# EVK-IRIS-W1-RMII.net
KiCad netlist of a schematic drawn in Altium Designer
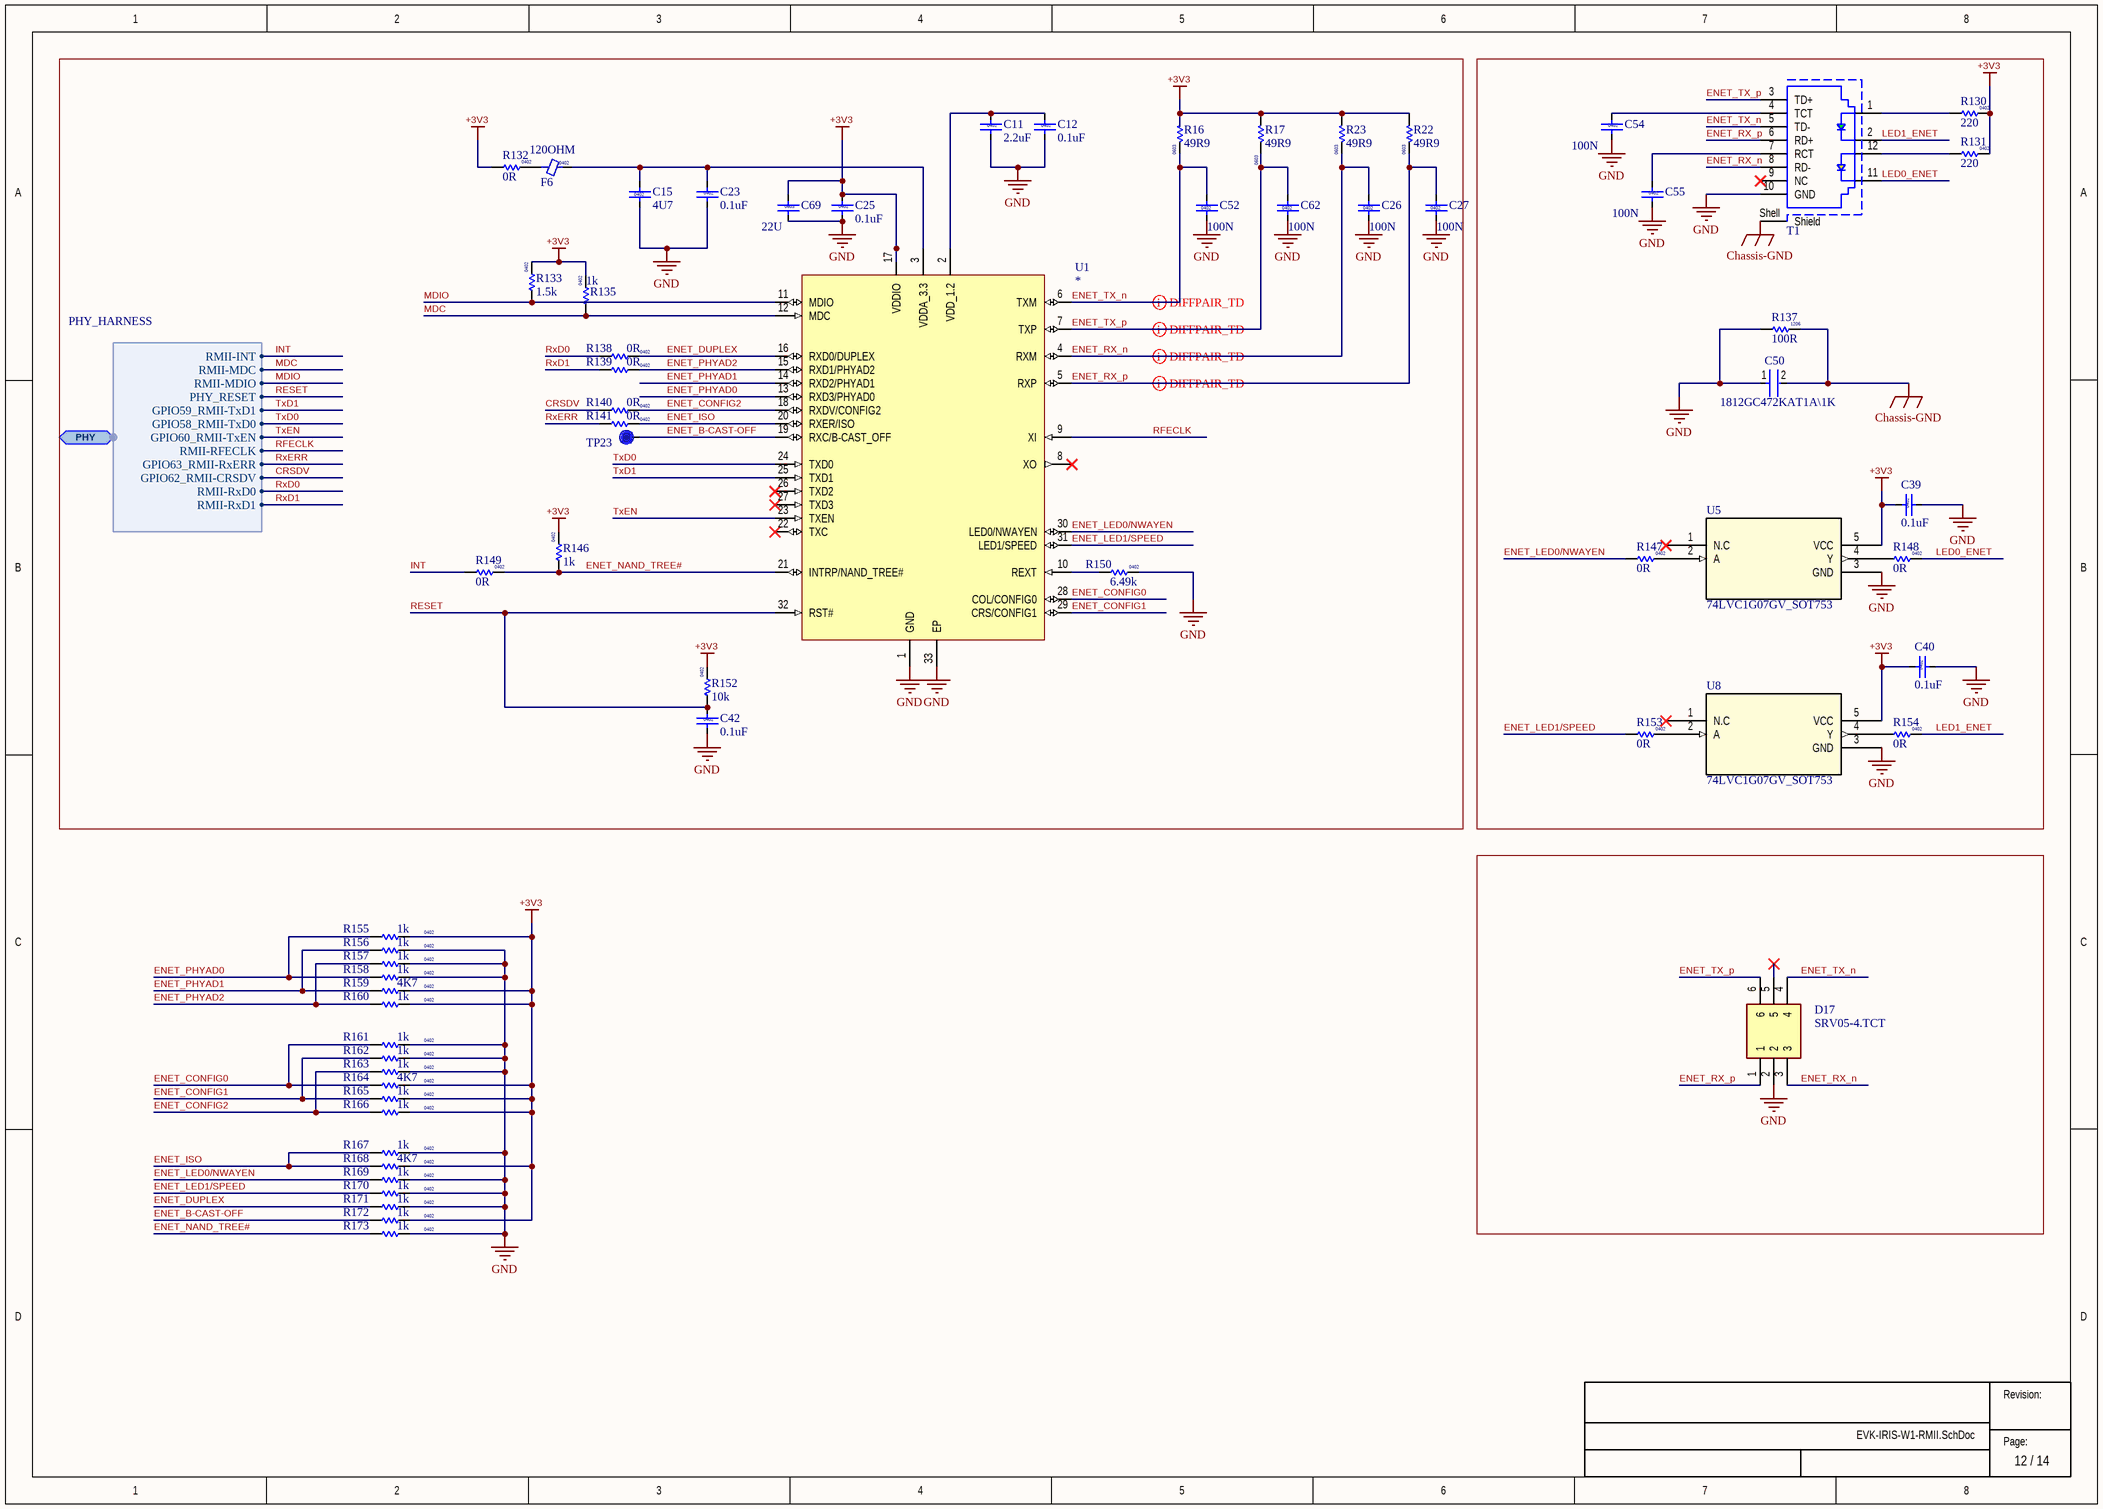
[diagram p0: EVK-IRIS-W1-RMII.SchDoc]

(export (version "E")
  (design (tool "Eeschema 10.0.6"))
  (components
    (comp (ref "C11")
      (value "2.2uF")
      (footprint "Cap 0402 HD")
      (description "Cap, Ceramic 2.2uF 6.3V 10% X5R 0402")
      (fields
        (field (name "SIZE") "0402")
        (field (name "PART NUMBER") "120-00042")
        (field (name "TOLERANCE") "+/- 10%")
      )
      (libsource (lib "Arena_Parts_DB_Lib") (part "Cap Chip"))
    )
    (comp (ref "C12")
      (value "0.1uF")
      (footprint "Cap 0402 HD")
      (description "Cap, Ceramic 0.1uF 10V 10% X5R 0402")
      (fields
        (field (name "SIZE") "0402")
        (field (name "PART NUMBER") "120-00016")
        (field (name "TOLERANCE") "+/- 10%")
      )
      (libsource (lib "Arena_Parts_DB_Lib") (part "Cap Chip"))
    )
    (comp (ref "C15")
      (value "4U7")
      (footprint "Cap_0402_1200Lx700Wx700H_600x600Pad_350G_FLX")
      (description "CAP CER X5R 0402 4U7 20% 10V")
      (fields
        (field (name "SIZE") "0402")
        (field (name "PART NUMBER") "UBXH01-0000243")
        (field (name "TOLERANCE") "20%")
        (field (name "EDITOR") "martin.pilik")
        (field (name "RELEASED BY") "fabrice.bret-dibat")
      )
      (libsource (lib "UBX_Parts_DB_Lib") (part "Cap Chip"))
    )
    (comp (ref "C23")
      (value "0.1uF")
      (footprint "Cap 0402 HD")
      (description "Cap, Ceramic 0.1uF 10V 10% X5R 0402")
      (fields
        (field (name "SIZE") "0402")
        (field (name "PART NUMBER") "120-00016")
        (field (name "TOLERANCE") "+/- 10%")
      )
      (libsource (lib "Arena_Parts_DB_Lib") (part "Cap Chip"))
    )
    (comp (ref "C25")
      (value "0.1uF")
      (footprint "Cap 0402 HD")
      (description "Cap, Ceramic 0.1uF 10V 10% X5R 0402")
      (fields
        (field (name "SIZE") "0402")
        (field (name "PART NUMBER") "120-00016")
        (field (name "TOLERANCE") "+/- 10%")
      )
      (libsource (lib "Arena_Parts_DB_Lib") (part "Cap Chip"))
    )
    (comp (ref "C26")
      (value "100N")
      (footprint "Cap 0402 HD")
      (description "CAP CER X7R 0402 100N 10% 16V")
      (fields
        (field (name "SIZE") "0402")
        (field (name "PART NUMBER") "UBXH01-0000233")
        (field (name "TOLERANCE") "10%")
        (field (name "EDITOR") "philippe.largier")
        (field (name "RELEASED BY") "charlotte.biber")
      )
      (libsource (lib "UBX_Parts_DB_Lib") (part "Cap Chip"))
    )
    (comp (ref "C27")
      (value "100N")
      (footprint "Cap 0402 HD")
      (description "CAP CER X7R 0402 100N 10% 16V")
      (fields
        (field (name "SIZE") "0402")
        (field (name "PART NUMBER") "UBXH01-0000233")
        (field (name "TOLERANCE") "10%")
        (field (name "EDITOR") "philippe.largier")
        (field (name "RELEASED BY") "charlotte.biber")
      )
      (libsource (lib "UBX_Parts_DB_Lib") (part "Cap Chip"))
    )
    (comp (ref "C39")
      (value "0.1uF")
      (footprint "Cap 0402 HD")
      (description "Cap, Ceramic 0.1uF 10V 10% X5R 0402")
      (fields
        (field (name "SIZE") "0402")
        (field (name "PART NUMBER") "120-00016")
        (field (name "TOLERANCE") "+/- 10%")
      )
      (libsource (lib "Arena_Parts_DB_Lib") (part "Cap Chip"))
    )
    (comp (ref "C40")
      (value "0.1uF")
      (footprint "Cap 0402 HD")
      (description "Cap, Ceramic 0.1uF 10V 10% X5R 0402")
      (fields
        (field (name "SIZE") "0402")
        (field (name "PART NUMBER") "120-00016")
        (field (name "TOLERANCE") "+/- 10%")
      )
      (libsource (lib "Arena_Parts_DB_Lib") (part "Cap Chip"))
    )
    (comp (ref "C42")
      (value "0.1uF")
      (footprint "Cap 0402 HD")
      (description "Cap, Ceramic 0.1uF 10V 10% X5R 0402")
      (fields
        (field (name "SIZE") "0402")
        (field (name "PART NUMBER") "120-00016")
        (field (name "TOLERANCE") "+/- 10%")
      )
      (libsource (lib "Arena_Parts_DB_Lib") (part "Cap Chip"))
    )
    (comp (ref "C50")
      (value "1812GC472KAT1~{A}1K")
      (footprint "FP-1812-L_4_6_0_5-W_3_2_0-MFG")
      (description "CAP CER 4700PF 2KV X7R 1812")
      (fields (field (name "VOLTAGE") "2kV") (field (name "TOLERANCE") "10%"))
      (libsource (lib "Altium Content Vault") (part "02cd4be3c70576c341d710602a673aa"))
    )
    (comp (ref "C52")
      (value "100N")
      (footprint "CAP 0402")
      (description "CAP CER X7R 0402 100N 10% 16V")
      (fields
        (field (name "SIZE") "0402")
        (field (name "PART NUMBER") "UBXH01-0000233")
        (field (name "TOLERANCE") "10%")
        (field (name "EDITOR") "philippe.largier")
        (field (name "RELEASED BY") "charlotte.biber")
      )
      (libsource (lib "UBX_Parts_DB_Lib") (part "Cap Chip"))
    )
    (comp (ref "C54")
      (value "100N")
      (footprint "Cap 0402")
      (description "CAP CER X7R 0402 100N 10% 16V")
      (fields
        (field (name "SIZE") "0402")
        (field (name "PART NUMBER") "UBXH01-0000233")
        (field (name "TOLERANCE") "10%")
        (field (name "EDITOR") "philippe.largier")
        (field (name "RELEASED BY") "charlotte.biber")
      )
      (libsource (lib "UBX_Parts_DB_Lib") (part "Cap Chip"))
    )
    (comp (ref "C55")
      (value "100N")
      (footprint "Cap 0402")
      (description "CAP CER X7R 0402 100N 10% 16V")
      (fields
        (field (name "SIZE") "0402")
        (field (name "PART NUMBER") "UBXH01-0000233")
        (field (name "TOLERANCE") "10%")
        (field (name "EDITOR") "philippe.largier")
        (field (name "RELEASED BY") "charlotte.biber")
      )
      (libsource (lib "UBX_Parts_DB_Lib") (part "Cap Chip"))
    )
    (comp (ref "C62")
      (value "100N")
      (footprint "CAP 0402")
      (description "CAP CER X7R 0402 100N 10% 16V")
      (fields
        (field (name "SIZE") "0402")
        (field (name "PART NUMBER") "UBXH01-0000233")
        (field (name "TOLERANCE") "10%")
        (field (name "EDITOR") "philippe.largier")
        (field (name "RELEASED BY") "charlotte.biber")
      )
      (libsource (lib "UBX_Parts_DB_Lib") (part "Cap Chip"))
    )
    (comp (ref "C69")
      (value "22U")
      (footprint "cap 0603")
      (description "CAP CER X5R 0603 22U 20% 4V")
      (fields
        (field (name "SIZE") "0603")
        (field (name "PART NUMBER") "UBXH01-0000041")
        (field (name "TOLERANCE") "20%")
        (field (name "EDITOR") "pierpaolo.arban")
      )
      (libsource (lib "UBX_Parts_DB_Lib") (part "Cap Chip"))
    )
    (comp (ref "D17")
      (value "SRV05-4.TCT")
      (footprint "SamacSys:SOT95P280X145-6N")
      (description "TVS Diode (Uni-directional)")
      (fields (field (name "MOUSER PART NUMBER") "947-SRV05-4.TCT"))
      (libsource (lib "*") (part "SRV05-4.TCT"))
    )
    (comp (ref "F6")
      (value "120OHM")
      (footprint "IND 0402")
      (description "FERRITE BEAD 0402 120 OHM AT 100MHZ 120OHM 500mA")
      (fields
        (field (name "SIZE") "0402")
        (field (name "PART NUMBER") "UBXH08-0000000")
        (field (name "MANUFACTURER") "TDK Corporation")
        (field (name "EDITOR") "roland.rust")
      )
      (libsource (lib "UBX_Parts_DB_Lib") (part "FB sm"))
    )
    (comp (ref "R16")
      (value "49R9")
      (footprint "RES 0603 HD")
      (description "RES THICK FILM CHIP 0603 49R9 1% 100mW")
      (fields
        (field (name "SIZE") "0603")
        (field (name "PART NUMBER") "UBXH18-0000118")
        (field (name "TOLERANCE") "1%")
        (field (name "EDITOR") "peter.mueller")
      )
      (libsource (lib "UBX_Parts_DB_Lib") (part "Res sm"))
    )
    (comp (ref "R17")
      (value "49R9")
      (footprint "RES 0603 HD")
      (description "RES THICK FILM CHIP 0603 49R9 1% 100mW")
      (fields
        (field (name "SIZE") "0603")
        (field (name "PART NUMBER") "UBXH18-0000118")
        (field (name "TOLERANCE") "1%")
        (field (name "EDITOR") "peter.mueller")
      )
      (libsource (lib "UBX_Parts_DB_Lib") (part "Res sm"))
    )
    (comp (ref "R22")
      (value "49R9")
      (footprint "RES 0603 HD")
      (description "RES THICK FILM CHIP 0603 49R9 1% 100mW")
      (fields
        (field (name "SIZE") "0603")
        (field (name "PART NUMBER") "UBXH18-0000118")
        (field (name "TOLERANCE") "1%")
        (field (name "EDITOR") "peter.mueller")
      )
      (libsource (lib "UBX_Parts_DB_Lib") (part "Res sm"))
    )
    (comp (ref "R23")
      (value "49R9")
      (footprint "RES 0603 HD")
      (description "RES THICK FILM CHIP 0603 49R9 1% 100mW")
      (fields
        (field (name "SIZE") "0603")
        (field (name "PART NUMBER") "UBXH18-0000118")
        (field (name "TOLERANCE") "1%")
        (field (name "EDITOR") "peter.mueller")
      )
      (libsource (lib "UBX_Parts_DB_Lib") (part "Res sm"))
    )
    (comp (ref "R130")
      (value "220")
      (footprint "RES 0402 HD")
      (description "Resistor, 220ohm, 1%, 1/16W, 0402")
      (fields
        (field (name "SIZE") "0402")
        (field (name "PART NUMBER") "180-00056")
        (field (name "POWER") "1/16W")
      )
      (libsource (lib "Arena_Parts_DB_Lib") (part "Res sm"))
    )
    (comp (ref "R131")
      (value "220")
      (footprint "RES 0402 HD")
      (description "Resistor, 220ohm, 1%, 1/16W, 0402")
      (fields
        (field (name "SIZE") "0402")
        (field (name "PART NUMBER") "180-00056")
        (field (name "POWER") "1/16W")
      )
      (libsource (lib "Arena_Parts_DB_Lib") (part "Res sm"))
    )
    (comp (ref "R132")
      (value "0R")
      (footprint "RES 0402 HD")
      (description "RES THICK FILM CHIP 0402 0R 0 100mW")
      (fields
        (field (name "SIZE") "0402")
        (field (name "PART NUMBER") "UBXH18-0003002")
        (field (name "TOLERANCE") "0")
        (field (name "EDITOR") "charlotte.biber")
        (field (name "RELEASED BY") "peter.mueller")
      )
      (libsource (lib "UBX_Parts_DB_Lib") (part "Res sm"))
    )
    (comp (ref "R133")
      (value "1.5k")
      (footprint "RES 0402 HD")
      (description "Resistor, 1.5Kohm, 1%, 1/16W, 0402")
      (fields
        (field (name "SIZE") "0402")
        (field (name "PART NUMBER") "180-00110")
        (field (name "POWER") "1/16W")
      )
      (libsource (lib "Arena_Parts_DB_Lib") (part "Res sm"))
    )
    (comp (ref "R135")
      (value "1k")
      (footprint "RES 0402 HD")
      (description "Resistor 1k ohm 1% 1/16W, 0402")
      (fields
        (field (name "SIZE") "0402")
        (field (name "PART NUMBER") "180-00021")
        (field (name "POWER") "1/16W")
      )
      (libsource (lib "Arena_Parts_DB_Lib") (part "Res sm"))
    )
    (comp (ref "R137")
      (value "100R")
      (footprint "RES 1206")
      (description "RES THICK FILM CHIP 1206 100R 0.1% 400mW")
      (fields
        (field (name "SIZE") "1206")
        (field (name "PART NUMBER") "UBXH18-0000460")
        (field (name "TOLERANCE") "0.1%")
        (field (name "EDITOR") "jernej.bufon")
        (field (name "RELEASED BY") "mikhail.sialitski")
      )
      (libsource (lib "UBX_Parts_DB_Lib") (part "Res sm"))
    )
    (comp (ref "R138")
      (value "0R")
      (footprint "RES 0402 HD")
      (description "RES THICK FILM CHIP 0402 0R 0 100mW")
      (fields
        (field (name "SIZE") "0402")
        (field (name "PART NUMBER") "UBXH18-0003002")
        (field (name "TOLERANCE") "0")
        (field (name "EDITOR") "charlotte.biber")
        (field (name "RELEASED BY") "peter.mueller")
      )
      (libsource (lib "UBX_Parts_DB_Lib") (part "Res sm"))
    )
    (comp (ref "R139")
      (value "0R")
      (footprint "RES 0402 HD")
      (description "RES THICK FILM CHIP 0402 0R 0 100mW")
      (fields
        (field (name "SIZE") "0402")
        (field (name "PART NUMBER") "UBXH18-0003002")
        (field (name "TOLERANCE") "0")
        (field (name "EDITOR") "charlotte.biber")
        (field (name "RELEASED BY") "peter.mueller")
      )
      (libsource (lib "UBX_Parts_DB_Lib") (part "Res sm"))
    )
    (comp (ref "R140")
      (value "0R")
      (footprint "RES 0402 HD")
      (description "RES THICK FILM CHIP 0402 0R 0 100mW")
      (fields
        (field (name "SIZE") "0402")
        (field (name "PART NUMBER") "UBXH18-0003002")
        (field (name "TOLERANCE") "0")
        (field (name "EDITOR") "charlotte.biber")
        (field (name "RELEASED BY") "peter.mueller")
      )
      (libsource (lib "UBX_Parts_DB_Lib") (part "Res sm"))
    )
    (comp (ref "R141")
      (value "0R")
      (footprint "RES 0402 HD")
      (description "RES THICK FILM CHIP 0402 0R 0 100mW")
      (fields
        (field (name "SIZE") "0402")
        (field (name "PART NUMBER") "UBXH18-0003002")
        (field (name "TOLERANCE") "0")
        (field (name "EDITOR") "charlotte.biber")
        (field (name "RELEASED BY") "peter.mueller")
      )
      (libsource (lib "UBX_Parts_DB_Lib") (part "Res sm"))
    )
    (comp (ref "R146")
      (value "1k")
      (footprint "RES 0402 HD")
      (description "Resistor 1k ohm 1% 1/16W, 0402")
      (fields
        (field (name "SIZE") "0402")
        (field (name "PART NUMBER") "180-00021")
        (field (name "POWER") "1/16W")
      )
      (libsource (lib "Arena_Parts_DB_Lib") (part "Res sm"))
    )
    (comp (ref "R147")
      (value "0R")
      (footprint "RES 0402 HD")
      (description "RES THICK FILM CHIP 0402 0R 0 100mW")
      (fields
        (field (name "SIZE") "0402")
        (field (name "PART NUMBER") "UBXH18-0003002")
        (field (name "TOLERANCE") "0")
        (field (name "EDITOR") "charlotte.biber")
        (field (name "RELEASED BY") "peter.mueller")
      )
      (libsource (lib "UBX_Parts_DB_Lib") (part "Res sm"))
    )
    (comp (ref "R148")
      (value "0R")
      (footprint "RES 0402 HD")
      (description "RES THICK FILM CHIP 0402 0R 0 100mW")
      (fields
        (field (name "SIZE") "0402")
        (field (name "PART NUMBER") "UBXH18-0003002")
        (field (name "TOLERANCE") "0")
        (field (name "EDITOR") "charlotte.biber")
        (field (name "RELEASED BY") "peter.mueller")
      )
      (libsource (lib "UBX_Parts_DB_Lib") (part "Res sm"))
    )
    (comp (ref "R149")
      (value "0R")
      (footprint "RES 0402 HD")
      (description "RES THICK FILM CHIP 0402 0R 0 100mW")
      (fields
        (field (name "SIZE") "0402")
        (field (name "PART NUMBER") "UBXH18-0003002")
        (field (name "TOLERANCE") "0")
        (field (name "EDITOR") "charlotte.biber")
        (field (name "RELEASED BY") "peter.mueller")
      )
      (libsource (lib "UBX_Parts_DB_Lib") (part "Res sm"))
    )
    (comp (ref "R150")
      (value "6.49k")
      (footprint "RES 0402 HD")
      (description "RES 6.49K OHM 1% 1/16W 0402")
      (fields
        (field (name "SIZE") "0402")
        (field (name "PART NUMBER") "180-00205")
        (field (name "POWER") "1/16W")
      )
      (libsource (lib "Arena_Parts_DB_Lib") (part "Res sm"))
    )
    (comp (ref "R152")
      (value "10k")
      (footprint "RES 0402 HD")
      (description "Resistor 10k ohm 1% 1/16W, 0402")
      (fields
        (field (name "SIZE") "0402")
        (field (name "PART NUMBER") "180-00024")
        (field (name "POWER") "1/16W")
      )
      (libsource (lib "Arena_Parts_DB_Lib") (part "Res sm"))
    )
    (comp (ref "R153")
      (value "0R")
      (footprint "RES 0402 HD")
      (description "RES THICK FILM CHIP 0402 0R 0 100mW")
      (fields
        (field (name "SIZE") "0402")
        (field (name "PART NUMBER") "UBXH18-0003002")
        (field (name "TOLERANCE") "0")
        (field (name "EDITOR") "charlotte.biber")
        (field (name "RELEASED BY") "peter.mueller")
      )
      (libsource (lib "UBX_Parts_DB_Lib") (part "Res sm"))
    )
    (comp (ref "R154")
      (value "0R")
      (footprint "RES 0402 HD")
      (description "RES THICK FILM CHIP 0402 0R 0 100mW")
      (fields
        (field (name "SIZE") "0402")
        (field (name "PART NUMBER") "UBXH18-0003002")
        (field (name "TOLERANCE") "0")
        (field (name "EDITOR") "charlotte.biber")
        (field (name "RELEASED BY") "peter.mueller")
      )
      (libsource (lib "UBX_Parts_DB_Lib") (part "Res sm"))
    )
    (comp (ref "R155")
      (value "1k")
      (footprint "RES 0402 HD")
      (description "Resistor 1k ohm 1% 1/16W, 0402")
      (fields
        (field (name "SIZE") "0402")
        (field (name "PART NUMBER") "180-00021")
        (field (name "POWER") "1/16W")
      )
      (libsource (lib "Arena_Parts_DB_Lib") (part "Res sm"))
    )
    (comp (ref "R156")
      (value "1k")
      (footprint "RES 0402 HD")
      (description "Resistor 1k ohm 1% 1/16W, 0402")
      (fields
        (field (name "SIZE") "0402")
        (field (name "PART NUMBER") "180-00021")
        (field (name "POWER") "1/16W")
      )
      (libsource (lib "Arena_Parts_DB_Lib") (part "Res sm"))
    )
    (comp (ref "R157")
      (value "1k")
      (footprint "RES 0402 HD")
      (description "Resistor 1k ohm 1% 1/16W, 0402")
      (fields
        (field (name "SIZE") "0402")
        (field (name "PART NUMBER") "180-00021")
        (field (name "POWER") "1/16W")
      )
      (libsource (lib "Arena_Parts_DB_Lib") (part "Res sm"))
    )
    (comp (ref "R158")
      (value "1k")
      (footprint "RES 0402 HD")
      (description "Resistor 1k ohm 1% 1/16W, 0402")
      (fields
        (field (name "SIZE") "0402")
        (field (name "PART NUMBER") "180-00021")
        (field (name "POWER") "1/16W")
      )
      (libsource (lib "Arena_Parts_DB_Lib") (part "Res sm"))
    )
    (comp (ref "R159")
      (value "4K7")
      (footprint "RES 0402 HD")
      (description "RES THICK FILM CHIP 0402 4K7 1% 63mW")
      (fields
        (field (name "SIZE") "0402")
        (field (name "PART NUMBER") "UBXH18-0000213")
        (field (name "TOLERANCE") "1%")
        (field (name "EDITOR") "michael.hein")
        (field (name "RELEASED BY") "vasyl.dykyy")
      )
      (libsource (lib "UBX_Parts_DB_Lib") (part "Res sm"))
    )
    (comp (ref "R160")
      (value "1k")
      (footprint "RES 0402 HD")
      (description "Resistor 1k ohm 1% 1/16W, 0402")
      (fields
        (field (name "SIZE") "0402")
        (field (name "PART NUMBER") "180-00021")
        (field (name "POWER") "1/16W")
      )
      (libsource (lib "Arena_Parts_DB_Lib") (part "Res sm"))
    )
    (comp (ref "R161")
      (value "1k")
      (footprint "RES 0402 HD")
      (description "Resistor 1k ohm 1% 1/16W, 0402")
      (fields
        (field (name "SIZE") "0402")
        (field (name "PART NUMBER") "180-00021")
        (field (name "POWER") "1/16W")
      )
      (libsource (lib "Arena_Parts_DB_Lib") (part "Res sm"))
    )
    (comp (ref "R162")
      (value "1k")
      (footprint "RES 0402 HD")
      (description "Resistor 1k ohm 1% 1/16W, 0402")
      (fields
        (field (name "SIZE") "0402")
        (field (name "PART NUMBER") "180-00021")
        (field (name "POWER") "1/16W")
      )
      (libsource (lib "Arena_Parts_DB_Lib") (part "Res sm"))
    )
    (comp (ref "R163")
      (value "1k")
      (footprint "RES 0402 HD")
      (description "Resistor 1k ohm 1% 1/16W, 0402")
      (fields
        (field (name "SIZE") "0402")
        (field (name "PART NUMBER") "180-00021")
        (field (name "POWER") "1/16W")
      )
      (libsource (lib "Arena_Parts_DB_Lib") (part "Res sm"))
    )
    (comp (ref "R164")
      (value "4K7")
      (footprint "RES 0402 HD")
      (description "RES THICK FILM CHIP 0402 4K7 1% 63mW")
      (fields
        (field (name "SIZE") "0402")
        (field (name "PART NUMBER") "UBXH18-0000213")
        (field (name "TOLERANCE") "1%")
        (field (name "EDITOR") "michael.hein")
        (field (name "RELEASED BY") "vasyl.dykyy")
      )
      (libsource (lib "UBX_Parts_DB_Lib") (part "Res sm"))
    )
    (comp (ref "R165")
      (value "1k")
      (footprint "RES 0402 HD")
      (description "Resistor 1k ohm 1% 1/16W, 0402")
      (fields
        (field (name "SIZE") "0402")
        (field (name "PART NUMBER") "180-00021")
        (field (name "POWER") "1/16W")
      )
      (libsource (lib "Arena_Parts_DB_Lib") (part "Res sm"))
    )
    (comp (ref "R166")
      (value "1k")
      (footprint "RES 0402 HD")
      (description "Resistor 1k ohm 1% 1/16W, 0402")
      (fields
        (field (name "SIZE") "0402")
        (field (name "PART NUMBER") "180-00021")
        (field (name "POWER") "1/16W")
      )
      (libsource (lib "Arena_Parts_DB_Lib") (part "Res sm"))
    )
    (comp (ref "R167")
      (value "1k")
      (footprint "RES 0402 HD")
      (description "Resistor 1k ohm 1% 1/16W, 0402")
      (fields
        (field (name "SIZE") "0402")
        (field (name "PART NUMBER") "180-00021")
        (field (name "POWER") "1/16W")
      )
      (libsource (lib "Arena_Parts_DB_Lib") (part "Res sm"))
    )
    (comp (ref "R168")
      (value "4K7")
      (footprint "RES 0402 HD")
      (description "RES THICK FILM CHIP 0402 4K7 1% 63mW")
      (fields
        (field (name "SIZE") "0402")
        (field (name "PART NUMBER") "UBXH18-0000213")
        (field (name "TOLERANCE") "1%")
        (field (name "EDITOR") "michael.hein")
        (field (name "RELEASED BY") "vasyl.dykyy")
      )
      (libsource (lib "UBX_Parts_DB_Lib") (part "Res sm"))
    )
    (comp (ref "R169")
      (value "1k")
      (footprint "RES 0402 HD")
      (description "Resistor 1k ohm 1% 1/16W, 0402")
      (fields
        (field (name "SIZE") "0402")
        (field (name "PART NUMBER") "180-00021")
        (field (name "POWER") "1/16W")
      )
      (libsource (lib "Arena_Parts_DB_Lib") (part "Res sm"))
    )
    (comp (ref "R170")
      (value "1k")
      (footprint "RES 0402 HD")
      (description "Resistor 1k ohm 1% 1/16W, 0402")
      (fields
        (field (name "SIZE") "0402")
        (field (name "PART NUMBER") "180-00021")
        (field (name "POWER") "1/16W")
      )
      (libsource (lib "Arena_Parts_DB_Lib") (part "Res sm"))
    )
    (comp (ref "R171")
      (value "1k")
      (footprint "RES 0402 HD")
      (description "Resistor 1k ohm 1% 1/16W, 0402")
      (fields
        (field (name "SIZE") "0402")
        (field (name "PART NUMBER") "180-00021")
        (field (name "POWER") "1/16W")
      )
      (libsource (lib "Arena_Parts_DB_Lib") (part "Res sm"))
    )
    (comp (ref "R172")
      (value "1k")
      (footprint "RES 0402 HD")
      (description "Resistor 1k ohm 1% 1/16W, 0402")
      (fields
        (field (name "SIZE") "0402")
        (field (name "PART NUMBER") "180-00021")
        (field (name "POWER") "1/16W")
      )
      (libsource (lib "Arena_Parts_DB_Lib") (part "Res sm"))
    )
    (comp (ref "R173")
      (value "1k")
      (footprint "RES 0402 HD")
      (description "Resistor 1k ohm 1% 1/16W, 0402")
      (fields
        (field (name "SIZE") "0402")
        (field (name "PART NUMBER") "180-00021")
        (field (name "POWER") "1/16W")
      )
      (libsource (lib "Arena_Parts_DB_Lib") (part "Res sm"))
    )
    (comp (ref "T1")
      (value "74980111211")
      (footprint "74980111211")
      (description "WE-RJ45 LAN Transformer, 1 Port, 10/100 Base-T, Tab Up")
      (fields (field (name "MANUFACTURER") "Wurth Elektronik"))
      (libsource (lib "WE-RJ45 LAN") (part "74980111211"))
    )
    (comp (ref "TP23")
      (value "TP")
      (footprint "TP10R")
      (description "Testpoint, Round 1.0mm Dia")
      (fields
        (field (name "PART NUMBER") "TP10R")
        (field (name "ADDED BY") "Jeremy D")
        (field (name "CHECKED BY") "Paul B")
      )
      (libsource (lib "LEGACY_Rigado_AltiumLib") (part "TP_R"))
    )
    (comp (ref "U1")
      (value "220-00037")
      (footprint "QFN0.5P8x8-32Pin_W-Pad")
      (description "IC TXRX ETHERNET 32QFN")
      (fields (field (name "MANUFACTURER P/N") "*") (field (name "VOLTAGE") "None"))
      (libsource (lib "Arena_Parts_DB_Lib") (part "KSZ8081RNB"))
    )
    (comp (ref "U5")
      (value "74LVC1G07GV_SOT753")
      (footprint "sot-753")
      (description "No Description Available")
      (fields (field (name "COPYRIGHT") "Copyright (C) 2023 Ultra Librarian. All rights reserved."))
      (libsource (lib "74LVC1G07GV_SOT753") (part "74LVC1G07GV_SOT753"))
    )
    (comp (ref "U8")
      (value "74LVC1G07GV_SOT753")
      (footprint "sot-753")
      (description "No Description Available")
      (fields (field (name "COPYRIGHT") "Copyright (C) 2023 Ultra Librarian. All rights reserved."))
      (libsource (lib "74LVC1G07GV_SOT753") (part "74LVC1G07GV_SOT753"))
    )
  )
  (nets
    (net (code "2") (name "+3V3") (class "Default")
      (node (ref "C25") (pin "1") (pinfunction "1_1") (pintype "passive"))
      (node (ref "C39") (pin "1") (pinfunction "1_1") (pintype "passive"))
      (node (ref "C40") (pin "1") (pinfunction "1_1") (pintype "passive"))
      (node (ref "C69") (pin "1") (pinfunction "1_1") (pintype "passive"))
      (node (ref "R130") (pin "2") (pinfunction "2_2") (pintype "passive"))
      (node (ref "R131") (pin "2") (pinfunction "2_2") (pintype "passive"))
      (node (ref "R132") (pin "1") (pinfunction "1_1") (pintype "passive"))
      (node (ref "R133") (pin "2") (pinfunction "2_2") (pintype "passive"))
      (node (ref "R135") (pin "2") (pinfunction "2_2") (pintype "passive"))
      (node (ref "R146") (pin "2") (pinfunction "2_2") (pintype "passive"))
      (node (ref "R152") (pin "2") (pinfunction "2_2") (pintype "passive"))
      (node (ref "R155") (pin "2") (pinfunction "2_2") (pintype "passive"))
      (node (ref "R159") (pin "2") (pinfunction "2_2") (pintype "passive"))
      (node (ref "R16") (pin "1") (pinfunction "1_1") (pintype "passive"))
      (node (ref "R160") (pin "2") (pinfunction "2_2") (pintype "passive"))
      (node (ref "R164") (pin "2") (pinfunction "2_2") (pintype "passive"))
      (node (ref "R165") (pin "2") (pinfunction "2_2") (pintype "passive"))
      (node (ref "R166") (pin "2") (pinfunction "2_2") (pintype "passive"))
      (node (ref "R168") (pin "2") (pinfunction "2_2") (pintype "passive"))
      (node (ref "R17") (pin "1") (pinfunction "1_1") (pintype "passive"))
      (node (ref "R172") (pin "2") (pinfunction "2_2") (pintype "passive"))
      (node (ref "R22") (pin "1") (pinfunction "1_1") (pintype "passive"))
      (node (ref "R23") (pin "1") (pinfunction "1_1") (pintype "passive"))
      (node (ref "U1") (pin "17") (pinfunction "VDDIO_17") (pintype "power_in"))
      (node (ref "U5") (pin "5") (pinfunction "VCC_5") (pintype "power_in"))
      (node (ref "U8") (pin "5") (pinfunction "VCC_5") (pintype "power_in"))
    )
    (net (code "3") (name "/CRSDV") (class "Default")
      (node (ref "R140") (pin "1") (pinfunction "1_1") (pintype "passive"))
    )
    (net (code "4") (name "/ENET_B-CAST-OFF") (class "Default")
      (node (ref "R172") (pin "1") (pinfunction "1_1") (pintype "passive"))
      (node (ref "TP23") (pin "1") (pintype "passive"))
      (node (ref "U1") (pin "19") (pinfunction "RXC/B-CAST_OFF_19") (pintype "bidirectional"))
    )
    (net (code "5") (name "/ENET_CONFIG0") (class "Default")
      (node (ref "R161") (pin "1") (pinfunction "1_1") (pintype "passive"))
      (node (ref "R164") (pin "1") (pinfunction "1_1") (pintype "passive"))
      (node (ref "U1") (pin "28") (pinfunction "COL/CONFIG0_28") (pintype "bidirectional"))
    )
    (net (code "6") (name "/ENET_CONFIG1") (class "Default")
      (node (ref "R162") (pin "1") (pinfunction "1_1") (pintype "passive"))
      (node (ref "R165") (pin "1") (pinfunction "1_1") (pintype "passive"))
      (node (ref "U1") (pin "29") (pinfunction "CRS/CONFIG1_29") (pintype "bidirectional"))
    )
    (net (code "7") (name "/ENET_CONFIG2") (class "Default")
      (node (ref "R140") (pin "2") (pinfunction "2_2") (pintype "passive"))
      (node (ref "R163") (pin "1") (pinfunction "1_1") (pintype "passive"))
      (node (ref "R166") (pin "1") (pinfunction "1_1") (pintype "passive"))
      (node (ref "U1") (pin "18") (pinfunction "RXDV/CONFIG2_18") (pintype "bidirectional"))
    )
    (net (code "8") (name "/ENET_DUPLEX") (class "Default")
      (node (ref "R138") (pin "2") (pinfunction "2_2") (pintype "passive"))
      (node (ref "R171") (pin "1") (pinfunction "1_1") (pintype "passive"))
      (node (ref "U1") (pin "16") (pinfunction "RXD0/DUPLEX_16") (pintype "bidirectional"))
    )
    (net (code "9") (name "/ENET_ISO") (class "Default")
      (node (ref "R141") (pin "2") (pinfunction "2_2") (pintype "passive"))
      (node (ref "R167") (pin "1") (pinfunction "1_1") (pintype "passive"))
      (node (ref "R168") (pin "1") (pinfunction "1_1") (pintype "passive"))
      (node (ref "U1") (pin "20") (pinfunction "RXER/ISO_20") (pintype "bidirectional"))
    )
    (net (code "10") (name "/ENET_LED0{slash}NWAYEN") (class "Default")
      (node (ref "R147") (pin "1") (pinfunction "1_1") (pintype "passive"))
      (node (ref "R169") (pin "1") (pinfunction "1_1") (pintype "passive"))
      (node (ref "U1") (pin "30") (pinfunction "LED0/NWAYEN_30") (pintype "bidirectional"))
    )
    (net (code "11") (name "/ENET_LED1{slash}SPEED") (class "Default")
      (node (ref "R153") (pin "1") (pinfunction "1_1") (pintype "passive"))
      (node (ref "R170") (pin "1") (pinfunction "1_1") (pintype "passive"))
      (node (ref "U1") (pin "31") (pinfunction "LED1/SPEED_31") (pintype "bidirectional"))
    )
    (net (code "12") (name "/ENET_NAND_TREE#") (class "Default")
      (node (ref "R146") (pin "1") (pinfunction "1_1") (pintype "passive"))
      (node (ref "R149") (pin "2") (pinfunction "2_2") (pintype "passive"))
      (node (ref "R173") (pin "1") (pinfunction "1_1") (pintype "passive"))
      (node (ref "U1") (pin "21") (pinfunction "INTRP/NAND_TREE#_21") (pintype "bidirectional"))
    )
    (net (code "13") (name "/ENET_PHYAD0") (class "Default")
      (node (ref "R155") (pin "1") (pinfunction "1_1") (pintype "passive"))
      (node (ref "R158") (pin "1") (pinfunction "1_1") (pintype "passive"))
      (node (ref "U1") (pin "13") (pinfunction "RXD3/PHYAD0_13") (pintype "bidirectional"))
    )
    (net (code "14") (name "/ENET_PHYAD1") (class "Default")
      (node (ref "R156") (pin "1") (pinfunction "1_1") (pintype "passive"))
      (node (ref "R159") (pin "1") (pinfunction "1_1") (pintype "passive"))
      (node (ref "U1") (pin "14") (pinfunction "RXD2/PHYAD1_14") (pintype "bidirectional"))
    )
    (net (code "15") (name "/ENET_PHYAD2") (class "Default")
      (node (ref "R139") (pin "2") (pinfunction "2_2") (pintype "passive"))
      (node (ref "R157") (pin "1") (pinfunction "1_1") (pintype "passive"))
      (node (ref "R160") (pin "1") (pinfunction "1_1") (pintype "passive"))
      (node (ref "U1") (pin "15") (pinfunction "RXD1/PHYAD2_15") (pintype "bidirectional"))
    )
    (net (code "16") (name "/ENET_RX_n") (class "Default")
      (node (ref "C26") (pin "2") (pinfunction "2_2") (pintype "passive"))
      (node (ref "D17") (pin "3") (pinfunction "3_3") (pintype "passive"))
      (node (ref "R23") (pin "2") (pinfunction "2_2") (pintype "passive"))
      (node (ref "T1") (pin "8") (pinfunction "RD-_8") (pintype "passive"))
      (node (ref "U1") (pin "4") (pinfunction "RXM_4") (pintype "bidirectional"))
    )
    (net (code "17") (name "/ENET_RX_p") (class "Default")
      (node (ref "C27") (pin "2") (pinfunction "2_2") (pintype "passive"))
      (node (ref "D17") (pin "1") (pinfunction "1_1") (pintype "passive"))
      (node (ref "R22") (pin "2") (pinfunction "2_2") (pintype "passive"))
      (node (ref "T1") (pin "6") (pinfunction "RD+_6") (pintype "passive"))
      (node (ref "U1") (pin "5") (pinfunction "RXP_5") (pintype "bidirectional"))
    )
    (net (code "18") (name "/ENET_TX_n") (class "Default")
      (node (ref "C52") (pin "1") (pinfunction "1_1") (pintype "passive"))
      (node (ref "D17") (pin "4") (pinfunction "4_4") (pintype "passive"))
      (node (ref "R16") (pin "2") (pinfunction "2_2") (pintype "passive"))
      (node (ref "T1") (pin "5") (pinfunction "TD-_5") (pintype "passive"))
      (node (ref "U1") (pin "6") (pinfunction "TXM_6") (pintype "bidirectional"))
    )
    (net (code "19") (name "/ENET_TX_p") (class "Default")
      (node (ref "C62") (pin "2") (pinfunction "2_2") (pintype "passive"))
      (node (ref "D17") (pin "6") (pinfunction "6_6") (pintype "passive"))
      (node (ref "R17") (pin "2") (pinfunction "2_2") (pintype "passive"))
      (node (ref "T1") (pin "3") (pinfunction "TD+_3") (pintype "passive"))
      (node (ref "U1") (pin "7") (pinfunction "TXP_7") (pintype "bidirectional"))
    )
    (net (code "20") (name "/INT") (class "Default")
      (node (ref "R149") (pin "1") (pinfunction "1_1") (pintype "passive"))
    )
    (net (code "21") (name "/LED0_ENET") (class "Default")
      (node (ref "R148") (pin "2") (pinfunction "2_2") (pintype "passive"))
      (node (ref "T1") (pin "11") (pinfunction "11_11") (pintype "passive"))
    )
    (net (code "22") (name "/LED1_ENET") (class "Default")
      (node (ref "R154") (pin "2") (pinfunction "2_2") (pintype "passive"))
      (node (ref "T1") (pin "2") (pinfunction "2_2") (pintype "passive"))
    )
    (net (code "23") (name "/MDC") (class "Default")
      (node (ref "R135") (pin "1") (pinfunction "1_1") (pintype "passive"))
      (node (ref "U1") (pin "12") (pinfunction "MDC_12") (pintype "input"))
    )
    (net (code "24") (name "/MDIO") (class "Default")
      (node (ref "R133") (pin "1") (pinfunction "1_1") (pintype "passive"))
      (node (ref "U1") (pin "11") (pinfunction "MDIO_11") (pintype "bidirectional"))
    )
    (net (code "25") (name "/RESET") (class "Default")
      (node (ref "C42") (pin "1") (pinfunction "1_1") (pintype "passive"))
      (node (ref "R152") (pin "1") (pinfunction "1_1") (pintype "passive"))
      (node (ref "U1") (pin "32") (pinfunction "RST#_32") (pintype "input"))
    )
    (net (code "26") (name "/RFECLK") (class "Default")
      (node (ref "U1") (pin "9") (pinfunction "XI_9") (pintype "input"))
    )
    (net (code "27") (name "/RxD0") (class "Default")
      (node (ref "R138") (pin "1") (pinfunction "1_1") (pintype "passive"))
    )
    (net (code "28") (name "/RxD1") (class "Default")
      (node (ref "R139") (pin "1") (pinfunction "1_1") (pintype "passive"))
    )
    (net (code "29") (name "/RxERR") (class "Default")
      (node (ref "R141") (pin "1") (pinfunction "1_1") (pintype "passive"))
    )
    (net (code "30") (name "/TxD0") (class "Default")
      (node (ref "U1") (pin "24") (pinfunction "TXD0_24") (pintype "input"))
    )
    (net (code "31") (name "/TxD1") (class "Default")
      (node (ref "U1") (pin "25") (pinfunction "TXD1_25") (pintype "input"))
    )
    (net (code "32") (name "/TxEN") (class "Default")
      (node (ref "U1") (pin "23") (pinfunction "TXEN_23") (pintype "input"))
    )
    (net (code "34") (name "Chassis-GND") (class "Default")
      (node (ref "C50") (pin "2") (pinfunction "2_2") (pintype "passive"))
      (node (ref "R137") (pin "2") (pinfunction "2_2") (pintype "passive"))
      (node (ref "T1") (pin "Shell") (pinfunction "Shield_Shell") (pintype "passive"))
    )
    (net (code "35") (name "GND") (class "Default")
      (node (ref "C11") (pin "2") (pinfunction "2_2") (pintype "passive"))
      (node (ref "C12") (pin "2") (pinfunction "2_2") (pintype "passive"))
      (node (ref "C15") (pin "2") (pinfunction "2_2") (pintype "passive"))
      (node (ref "C23") (pin "2") (pinfunction "2_2") (pintype "passive"))
      (node (ref "C25") (pin "2") (pinfunction "2_2") (pintype "passive"))
      (node (ref "C26") (pin "1") (pinfunction "1_1") (pintype "passive"))
      (node (ref "C27") (pin "1") (pinfunction "1_1") (pintype "passive"))
      (node (ref "C39") (pin "2") (pinfunction "2_2") (pintype "passive"))
      (node (ref "C40") (pin "2") (pinfunction "2_2") (pintype "passive"))
      (node (ref "C42") (pin "2") (pinfunction "2_2") (pintype "passive"))
      (node (ref "C50") (pin "1") (pinfunction "1_1") (pintype "passive"))
      (node (ref "C52") (pin "2") (pinfunction "2_2") (pintype "passive"))
      (node (ref "C54") (pin "2") (pinfunction "2_2") (pintype "passive"))
      (node (ref "C55") (pin "2") (pinfunction "2_2") (pintype "passive"))
      (node (ref "C62") (pin "1") (pinfunction "1_1") (pintype "passive"))
      (node (ref "C69") (pin "2") (pinfunction "2_2") (pintype "passive"))
      (node (ref "D17") (pin "2") (pinfunction "2_2") (pintype "passive"))
      (node (ref "R137") (pin "1") (pinfunction "1_1") (pintype "passive"))
      (node (ref "R150") (pin "2") (pinfunction "2_2") (pintype "passive"))
      (node (ref "R156") (pin "2") (pinfunction "2_2") (pintype "passive"))
      (node (ref "R157") (pin "2") (pinfunction "2_2") (pintype "passive"))
      (node (ref "R158") (pin "2") (pinfunction "2_2") (pintype "passive"))
      (node (ref "R161") (pin "2") (pinfunction "2_2") (pintype "passive"))
      (node (ref "R162") (pin "2") (pinfunction "2_2") (pintype "passive"))
      (node (ref "R163") (pin "2") (pinfunction "2_2") (pintype "passive"))
      (node (ref "R167") (pin "2") (pinfunction "2_2") (pintype "passive"))
      (node (ref "R169") (pin "2") (pinfunction "2_2") (pintype "passive"))
      (node (ref "R170") (pin "2") (pinfunction "2_2") (pintype "passive"))
      (node (ref "R171") (pin "2") (pinfunction "2_2") (pintype "passive"))
      (node (ref "R173") (pin "2") (pinfunction "2_2") (pintype "passive"))
      (node (ref "T1") (pin "10") (pinfunction "GND_10") (pintype "passive"))
      (node (ref "U1") (pin "1") (pinfunction "GND_1") (pintype "power_in"))
      (node (ref "U1") (pin "33") (pinfunction "EP_33") (pintype "power_in"))
      (node (ref "U5") (pin "3") (pinfunction "GND_3") (pintype "passive"))
      (node (ref "U8") (pin "3") (pinfunction "GND_3") (pintype "passive"))
    )
    (net (code "36") (name "Net-(F6-Pad1)") (class "Default")
      (node (ref "F6") (pin "1") (pinfunction "1_1") (pintype "passive"))
      (node (ref "R132") (pin "2") (pinfunction "2_2") (pintype "passive"))
    )
    (net (code "37") (name "Net-(R130-Pad1)") (class "Default")
      (node (ref "R130") (pin "1") (pinfunction "1_1") (pintype "passive"))
      (node (ref "T1") (pin "1") (pinfunction "1_1") (pintype "passive"))
    )
    (net (code "38") (name "Net-(R131-Pad1)") (class "Default")
      (node (ref "R131") (pin "1") (pinfunction "1_1") (pintype "passive"))
      (node (ref "T1") (pin "12") (pinfunction "12_12") (pintype "passive"))
    )
    (net (code "39") (name "Net-(T1-RCT)") (class "Default")
      (node (ref "C55") (pin "1") (pinfunction "1_1") (pintype "passive"))
      (node (ref "T1") (pin "7") (pinfunction "RCT_7") (pintype "passive"))
    )
    (net (code "40") (name "Net-(T1-TCT)") (class "Default")
      (node (ref "C54") (pin "1") (pinfunction "1_1") (pintype "passive"))
      (node (ref "T1") (pin "4") (pinfunction "TCT_4") (pintype "passive"))
    )
    (net (code "41") (name "Net-(U1-REXT)") (class "Default")
      (node (ref "R150") (pin "1") (pinfunction "1_1") (pintype "passive"))
      (node (ref "U1") (pin "10") (pinfunction "REXT_10") (pintype "input"))
    )
    (net (code "42") (name "Net-(U1-VDDA_3.3)") (class "Default")
      (node (ref "C15") (pin "1") (pinfunction "1_1") (pintype "passive"))
      (node (ref "C23") (pin "1") (pinfunction "1_1") (pintype "passive"))
      (node (ref "F6") (pin "2") (pinfunction "2_2") (pintype "passive"))
      (node (ref "U1") (pin "3") (pinfunction "VDDA_3.3_3") (pintype "power_in"))
    )
    (net (code "43") (name "Net-(U1-VDD_1.2)") (class "Default")
      (node (ref "C11") (pin "1") (pinfunction "1_1") (pintype "passive"))
      (node (ref "C12") (pin "1") (pinfunction "1_1") (pintype "passive"))
      (node (ref "U1") (pin "2") (pinfunction "VDD_1.2_2") (pintype "power_in"))
    )
    (net (code "44") (name "Net-(U5-A)") (class "Default")
      (node (ref "R147") (pin "2") (pinfunction "2_2") (pintype "passive"))
      (node (ref "U5") (pin "2") (pinfunction "A_2") (pintype "input"))
    )
    (net (code "45") (name "Net-(U5-Y)") (class "Default")
      (node (ref "R148") (pin "1") (pinfunction "1_1") (pintype "passive"))
      (node (ref "U5") (pin "4") (pinfunction "Y_4") (pintype "output"))
    )
    (net (code "46") (name "Net-(U8-A)") (class "Default")
      (node (ref "R153") (pin "2") (pinfunction "2_2") (pintype "passive"))
      (node (ref "U8") (pin "2") (pinfunction "A_2") (pintype "input"))
    )
    (net (code "47") (name "Net-(U8-Y)") (class "Default")
      (node (ref "R154") (pin "1") (pinfunction "1_1") (pintype "passive"))
      (node (ref "U8") (pin "4") (pinfunction "Y_4") (pintype "output"))
    )
    (net (code "48") (name "unconnected-(D17-Pad5)") (class "Default")
      (node (ref "D17") (pin "5") (pinfunction "5_5") (pintype "passive+no_connect"))
    )
    (net (code "49") (name "unconnected-(T1-NC-Pad9)") (class "Default")
      (node (ref "T1") (pin "9") (pinfunction "NC_9") (pintype "passive+no_connect"))
    )
    (net (code "50") (name "unconnected-(U1-TXC-Pad22)") (class "Default")
      (node (ref "U1") (pin "22") (pinfunction "TXC_22") (pintype "bidirectional+no_connect"))
    )
    (net (code "51") (name "unconnected-(U1-TXD2-Pad26)") (class "Default")
      (node (ref "U1") (pin "26") (pinfunction "TXD2_26") (pintype "input+no_connect"))
    )
    (net (code "52") (name "unconnected-(U1-TXD3-Pad27)") (class "Default")
      (node (ref "U1") (pin "27") (pinfunction "TXD3_27") (pintype "input+no_connect"))
    )
    (net (code "53") (name "unconnected-(U1-XO-Pad8)") (class "Default")
      (node (ref "U1") (pin "8") (pinfunction "XO_8") (pintype "output+no_connect"))
    )
    (net (code "54") (name "unconnected-(U5-N.C-Pad1)") (class "Default")
      (node (ref "U5") (pin "1") (pinfunction "N.C_1") (pintype "passive+no_connect"))
    )
    (net (code "55") (name "unconnected-(U8-N.C-Pad1)") (class "Default")
      (node (ref "U8") (pin "1") (pinfunction "N.C_1") (pintype "passive+no_connect"))
    )
  )
)
